# modulo_motores.net
KiCad netlist of a schematic drawn in EAGLE
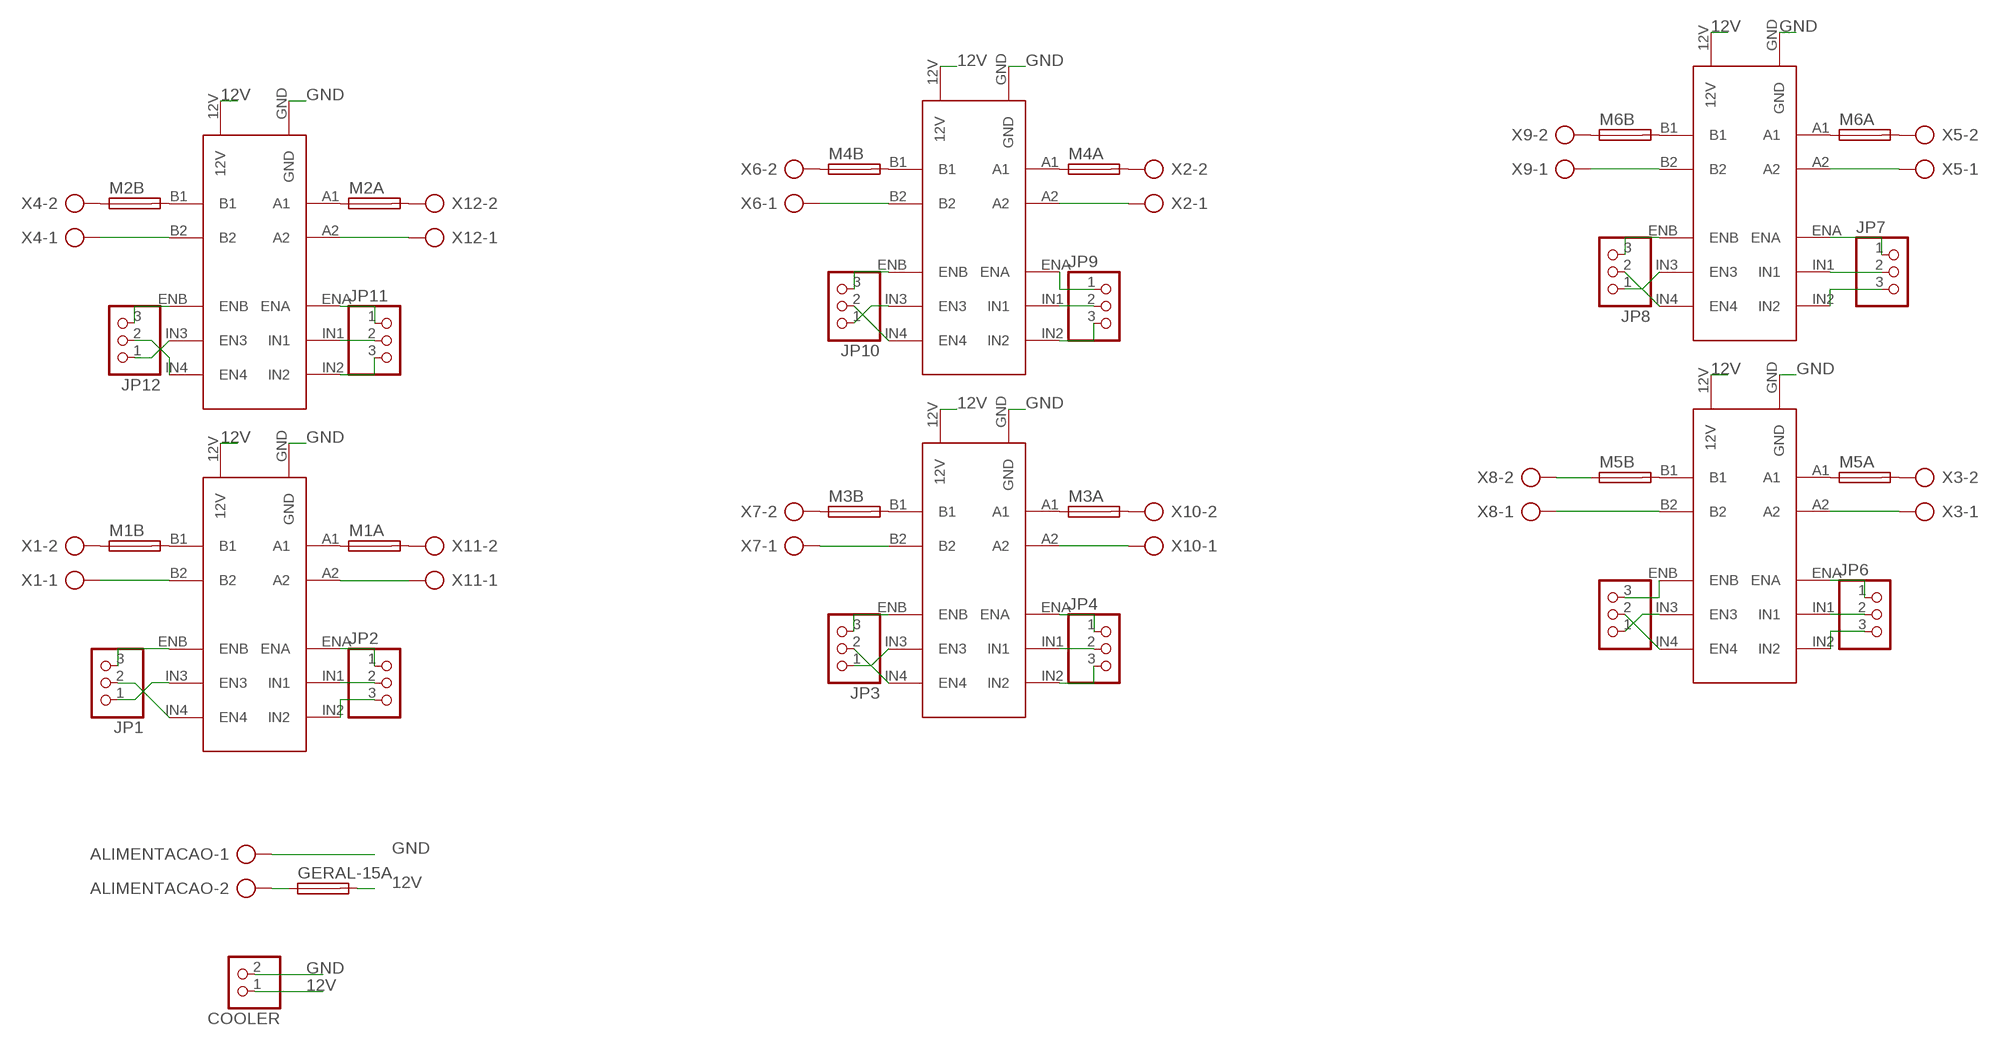
[diagram p0: schematic, sheet 1]

(export (version "E")
  (design (tool "Eeschema 10.0.6"))
  (components
    (comp (ref "ALIMENTACAO")
      (value "AK500/2")
      (footprint "eagle-import:AK500_2")
      (libsource (lib "eagle-import") (part "AK500/2"))
    )
    (comp (ref "COOLER")
      (value "PINHD-1X2")
      (footprint "eagle-import:1X02")
      (libsource (lib "eagle-import") (part "PINHD-1X2"))
    )
    (comp (ref "GERAL-15A")
      (value "SH22,5A")
      (footprint "eagle-import:SH22,5A")
      (fields (field (name "MPN") "0031.7701.11"))
      (libsource (lib "eagle-import") (part "SH22,5A"))
    )
    (comp (ref "JP1")
      (value "PINHD-1X3")
      (footprint "eagle-import:1X03")
      (libsource (lib "eagle-import") (part "PINHD-1X3"))
    )
    (comp (ref "JP2")
      (value "PINHD-1X3")
      (footprint "eagle-import:1X03")
      (libsource (lib "eagle-import") (part "PINHD-1X3"))
    )
    (comp (ref "JP3")
      (value "PINHD-1X3")
      (footprint "eagle-import:1X03")
      (libsource (lib "eagle-import") (part "PINHD-1X3"))
    )
    (comp (ref "JP4")
      (value "PINHD-1X3")
      (footprint "eagle-import:1X03")
      (libsource (lib "eagle-import") (part "PINHD-1X3"))
    )
    (comp (ref "JP5")
      (value "PINHD-1X3")
      (footprint "eagle-import:1X03")
      (libsource (lib "eagle-import") (part "PINHD-1X3"))
    )
    (comp (ref "JP6")
      (value "PINHD-1X3")
      (footprint "eagle-import:1X03")
      (libsource (lib "eagle-import") (part "PINHD-1X3"))
    )
    (comp (ref "JP7")
      (value "PINHD-1X3")
      (footprint "eagle-import:1X03")
      (libsource (lib "eagle-import") (part "PINHD-1X3"))
    )
    (comp (ref "JP8")
      (value "PINHD-1X3")
      (footprint "eagle-import:1X03")
      (libsource (lib "eagle-import") (part "PINHD-1X3"))
    )
    (comp (ref "JP9")
      (value "PINHD-1X3")
      (footprint "eagle-import:1X03")
      (libsource (lib "eagle-import") (part "PINHD-1X3"))
    )
    (comp (ref "JP10")
      (value "PINHD-1X3")
      (footprint "eagle-import:1X03")
      (libsource (lib "eagle-import") (part "PINHD-1X3"))
    )
    (comp (ref "JP11")
      (value "PINHD-1X3")
      (footprint "eagle-import:1X03")
      (libsource (lib "eagle-import") (part "PINHD-1X3"))
    )
    (comp (ref "JP12")
      (value "PINHD-1X3")
      (footprint "eagle-import:1X03")
      (libsource (lib "eagle-import") (part "PINHD-1X3"))
    )
    (comp (ref "M1")
      (value "L298N")
      (footprint "eagle-import:L298N")
      (libsource (lib "eagle-import") (part "L298N"))
    )
    (comp (ref "M1A")
      (value "SH22,5A")
      (footprint "eagle-import:SH22,5A")
      (fields (field (name "MPN") "0031.7701.11"))
      (libsource (lib "eagle-import") (part "SH22,5A"))
    )
    (comp (ref "M1B")
      (value "SH22,5A")
      (footprint "eagle-import:SH22,5A")
      (fields (field (name "MPN") "0031.7701.11"))
      (libsource (lib "eagle-import") (part "SH22,5A"))
    )
    (comp (ref "M2")
      (value "L298N")
      (footprint "eagle-import:L298N")
      (libsource (lib "eagle-import") (part "L298N"))
    )
    (comp (ref "M2A")
      (value "SH22,5A")
      (footprint "eagle-import:SH22,5A")
      (fields (field (name "MPN") "0031.7701.11"))
      (libsource (lib "eagle-import") (part "SH22,5A"))
    )
    (comp (ref "M2B")
      (value "SH22,5A")
      (footprint "eagle-import:SH22,5A")
      (fields (field (name "MPN") "0031.7701.11"))
      (libsource (lib "eagle-import") (part "SH22,5A"))
    )
    (comp (ref "M3")
      (value "L298N")
      (footprint "eagle-import:L298N")
      (libsource (lib "eagle-import") (part "L298N"))
    )
    (comp (ref "M3A")
      (value "SH22,5A")
      (footprint "eagle-import:SH22,5A")
      (fields (field (name "MPN") "0031.7701.11"))
      (libsource (lib "eagle-import") (part "SH22,5A"))
    )
    (comp (ref "M3B")
      (value "SH22,5A")
      (footprint "eagle-import:SH22,5A")
      (fields (field (name "MPN") "0031.7701.11"))
      (libsource (lib "eagle-import") (part "SH22,5A"))
    )
    (comp (ref "M4A")
      (value "SH22,5A")
      (footprint "eagle-import:SH22,5A")
      (fields (field (name "MPN") "0031.7701.11"))
      (libsource (lib "eagle-import") (part "SH22,5A"))
    )
    (comp (ref "M4B")
      (value "SH22,5A")
      (footprint "eagle-import:SH22,5A")
      (fields (field (name "MPN") "0031.7701.11"))
      (libsource (lib "eagle-import") (part "SH22,5A"))
    )
    (comp (ref "M5")
      (value "L298N")
      (footprint "eagle-import:L298N")
      (libsource (lib "eagle-import") (part "L298N"))
    )
    (comp (ref "M5A")
      (value "SH22,5A")
      (footprint "eagle-import:SH22,5A")
      (fields (field (name "MPN") "0031.7701.11"))
      (libsource (lib "eagle-import") (part "SH22,5A"))
    )
    (comp (ref "M5B")
      (value "SH22,5A")
      (footprint "eagle-import:SH22,5A")
      (fields (field (name "MPN") "0031.7701.11"))
      (libsource (lib "eagle-import") (part "SH22,5A"))
    )
    (comp (ref "M6")
      (value "L298N")
      (footprint "eagle-import:L298N")
      (libsource (lib "eagle-import") (part "L298N"))
    )
    (comp (ref "M6A")
      (value "SH22,5A")
      (footprint "eagle-import:SH22,5A")
      (fields (field (name "MPN") "0031.7701.11"))
      (libsource (lib "eagle-import") (part "SH22,5A"))
    )
    (comp (ref "M6B")
      (value "SH22,5A")
      (footprint "eagle-import:SH22,5A")
      (fields (field (name "MPN") "0031.7701.11"))
      (libsource (lib "eagle-import") (part "SH22,5A"))
    )
    (comp (ref "U$2")
      (value "L298N")
      (footprint "eagle-import:L298N")
      (libsource (lib "eagle-import") (part "L298N"))
    )
    (comp (ref "X1")
      (value "AK500/2")
      (footprint "eagle-import:AK500_2")
      (libsource (lib "eagle-import") (part "AK500/2"))
    )
    (comp (ref "X2")
      (value "AK500/2")
      (footprint "eagle-import:AK500_2")
      (libsource (lib "eagle-import") (part "AK500/2"))
    )
    (comp (ref "X3")
      (value "AK500/2")
      (footprint "eagle-import:AK500_2")
      (libsource (lib "eagle-import") (part "AK500/2"))
    )
    (comp (ref "X4")
      (value "AK500/2")
      (footprint "eagle-import:AK500_2")
      (libsource (lib "eagle-import") (part "AK500/2"))
    )
    (comp (ref "X5")
      (value "AK500/2")
      (footprint "eagle-import:AK500_2")
      (libsource (lib "eagle-import") (part "AK500/2"))
    )
    (comp (ref "X6")
      (value "AK500/2")
      (footprint "eagle-import:AK500_2")
      (libsource (lib "eagle-import") (part "AK500/2"))
    )
    (comp (ref "X7")
      (value "AK500/2")
      (footprint "eagle-import:AK500_2")
      (libsource (lib "eagle-import") (part "AK500/2"))
    )
    (comp (ref "X8")
      (value "AK500/2")
      (footprint "eagle-import:AK500_2")
      (libsource (lib "eagle-import") (part "AK500/2"))
    )
    (comp (ref "X9")
      (value "AK500/2")
      (footprint "eagle-import:AK500_2")
      (libsource (lib "eagle-import") (part "AK500/2"))
    )
    (comp (ref "X10")
      (value "AK500/2")
      (footprint "eagle-import:AK500_2")
      (libsource (lib "eagle-import") (part "AK500/2"))
    )
    (comp (ref "X11")
      (value "AK500/2")
      (footprint "eagle-import:AK500_2")
      (libsource (lib "eagle-import") (part "AK500/2"))
    )
    (comp (ref "X12")
      (value "AK500/2")
      (footprint "eagle-import:AK500_2")
      (libsource (lib "eagle-import") (part "AK500/2"))
    )
  )
  (nets
    (net (code "1") (name "/12V") (class "Default")
      (node (ref "COOLER") (pin "1") (pinfunction "1_1") (pintype "passive"))
      (node (ref "GERAL-15A") (pin "2") (pinfunction "2_2") (pintype "passive"))
      (node (ref "M1") (pin "12V") (pinfunction "12V_12V") (pintype "bidirectional"))
      (node (ref "M2") (pin "12V") (pinfunction "12V_12V") (pintype "bidirectional"))
      (node (ref "M3") (pin "12V") (pinfunction "12V_12V") (pintype "bidirectional"))
      (node (ref "M5") (pin "12V") (pinfunction "12V_12V") (pintype "bidirectional"))
      (node (ref "M6") (pin "12V") (pinfunction "12V_12V") (pintype "bidirectional"))
      (node (ref "U$2") (pin "12V") (pinfunction "12V_12V") (pintype "bidirectional"))
    )
    (net (code "2") (name "/GND") (class "Default")
      (node (ref "ALIMENTACAO") (pin "1") (pinfunction "KL_1") (pintype "passive"))
      (node (ref "COOLER") (pin "2") (pinfunction "2_2") (pintype "passive"))
      (node (ref "M1") (pin "GND") (pinfunction "GND_GND") (pintype "bidirectional"))
      (node (ref "M2") (pin "GND") (pinfunction "GND_GND") (pintype "bidirectional"))
      (node (ref "M3") (pin "GND") (pinfunction "GND_GND") (pintype "bidirectional"))
      (node (ref "M5") (pin "GND") (pinfunction "GND_GND") (pintype "bidirectional"))
      (node (ref "M6") (pin "GND") (pinfunction "GND_GND") (pintype "bidirectional"))
      (node (ref "U$2") (pin "GND") (pinfunction "GND_GND") (pintype "bidirectional"))
    )
    (net (code "3") (name "Net-(ALIMENTACAOB-KL)") (class "Default")
      (node (ref "ALIMENTACAO") (pin "2") (pinfunction "KL_2") (pintype "passive"))
      (node (ref "GERAL-15A") (pin "1") (pinfunction "1_1") (pintype "passive"))
    )
    (net (code "4") (name "Net-(JP1-Pad3)") (class "Default")
      (node (ref "JP1") (pin "3") (pinfunction "3_3") (pintype "passive"))
      (node (ref "M1") (pin "ENB") (pinfunction "ENB_ENB") (pintype "bidirectional"))
    )
    (net (code "5") (name "Net-(JP2-Pad1)") (class "Default")
      (node (ref "JP2") (pin "1") (pinfunction "1_1") (pintype "passive"))
      (node (ref "M1") (pin "ENA") (pinfunction "ENA_ENA") (pintype "bidirectional"))
    )
    (net (code "6") (name "Net-(JP2-Pad2)") (class "Default")
      (node (ref "JP2") (pin "2") (pinfunction "2_2") (pintype "passive"))
      (node (ref "M1") (pin "IN1") (pinfunction "IN1_IN1") (pintype "bidirectional"))
    )
    (net (code "7") (name "Net-(JP2-Pad3)") (class "Default")
      (node (ref "JP2") (pin "3") (pinfunction "3_3") (pintype "passive"))
      (node (ref "M1") (pin "IN2") (pinfunction "IN2_IN2") (pintype "bidirectional"))
    )
    (net (code "8") (name "Net-(JP3-Pad3)") (class "Default")
      (node (ref "JP3") (pin "3") (pinfunction "3_3") (pintype "passive"))
      (node (ref "M3") (pin "ENB") (pinfunction "ENB_ENB") (pintype "bidirectional"))
    )
    (net (code "9") (name "Net-(JP4-Pad1)") (class "Default")
      (node (ref "JP4") (pin "1") (pinfunction "1_1") (pintype "passive"))
      (node (ref "M3") (pin "ENA") (pinfunction "ENA_ENA") (pintype "bidirectional"))
    )
    (net (code "10") (name "Net-(JP4-Pad2)") (class "Default")
      (node (ref "JP4") (pin "2") (pinfunction "2_2") (pintype "passive"))
      (node (ref "M3") (pin "IN1") (pinfunction "IN1_IN1") (pintype "bidirectional"))
    )
    (net (code "11") (name "Net-(JP4-Pad3)") (class "Default")
      (node (ref "JP4") (pin "3") (pinfunction "3_3") (pintype "passive"))
      (node (ref "M3") (pin "IN2") (pinfunction "IN2_IN2") (pintype "bidirectional"))
    )
    (net (code "12") (name "Net-(JP5-Pad3)") (class "Default")
      (node (ref "JP5") (pin "3") (pinfunction "3_3") (pintype "passive"))
      (node (ref "M5") (pin "ENB") (pinfunction "ENB_ENB") (pintype "bidirectional"))
    )
    (net (code "13") (name "Net-(JP6-Pad1)") (class "Default")
      (node (ref "JP6") (pin "1") (pinfunction "1_1") (pintype "passive"))
      (node (ref "M5") (pin "ENA") (pinfunction "ENA_ENA") (pintype "bidirectional"))
    )
    (net (code "14") (name "Net-(JP6-Pad2)") (class "Default")
      (node (ref "JP6") (pin "2") (pinfunction "2_2") (pintype "passive"))
      (node (ref "M5") (pin "IN1") (pinfunction "IN1_IN1") (pintype "bidirectional"))
    )
    (net (code "15") (name "Net-(JP6-Pad3)") (class "Default")
      (node (ref "JP6") (pin "3") (pinfunction "3_3") (pintype "passive"))
      (node (ref "M5") (pin "IN2") (pinfunction "IN2_IN2") (pintype "bidirectional"))
    )
    (net (code "16") (name "Net-(JP7-Pad1)") (class "Default")
      (node (ref "JP7") (pin "1") (pinfunction "1_1") (pintype "passive"))
      (node (ref "M6") (pin "ENA") (pinfunction "ENA_ENA") (pintype "bidirectional"))
    )
    (net (code "17") (name "Net-(JP7-Pad2)") (class "Default")
      (node (ref "JP7") (pin "2") (pinfunction "2_2") (pintype "passive"))
      (node (ref "M6") (pin "IN1") (pinfunction "IN1_IN1") (pintype "bidirectional"))
    )
    (net (code "18") (name "Net-(JP7-Pad3)") (class "Default")
      (node (ref "JP7") (pin "3") (pinfunction "3_3") (pintype "passive"))
      (node (ref "M6") (pin "IN2") (pinfunction "IN2_IN2") (pintype "bidirectional"))
    )
    (net (code "19") (name "Net-(JP8-Pad3)") (class "Default")
      (node (ref "JP8") (pin "3") (pinfunction "3_3") (pintype "passive"))
      (node (ref "M6") (pin "ENB") (pinfunction "ENB_ENB") (pintype "bidirectional"))
    )
    (net (code "20") (name "Net-(JP9-Pad1)") (class "Default")
      (node (ref "JP9") (pin "1") (pinfunction "1_1") (pintype "passive"))
      (node (ref "U$2") (pin "ENA") (pinfunction "ENA_ENA") (pintype "bidirectional"))
    )
    (net (code "21") (name "Net-(JP9-Pad2)") (class "Default")
      (node (ref "JP9") (pin "2") (pinfunction "2_2") (pintype "passive"))
      (node (ref "U$2") (pin "IN1") (pinfunction "IN1_IN1") (pintype "bidirectional"))
    )
    (net (code "22") (name "Net-(JP9-Pad3)") (class "Default")
      (node (ref "JP9") (pin "3") (pinfunction "3_3") (pintype "passive"))
      (node (ref "U$2") (pin "IN2") (pinfunction "IN2_IN2") (pintype "bidirectional"))
    )
    (net (code "23") (name "Net-(JP10-Pad3)") (class "Default")
      (node (ref "JP10") (pin "3") (pinfunction "3_3") (pintype "passive"))
      (node (ref "U$2") (pin "ENB") (pinfunction "ENB_ENB") (pintype "bidirectional"))
    )
    (net (code "24") (name "Net-(JP11-Pad1)") (class "Default")
      (node (ref "JP11") (pin "1") (pinfunction "1_1") (pintype "passive"))
      (node (ref "M2") (pin "ENA") (pinfunction "ENA_ENA") (pintype "bidirectional"))
    )
    (net (code "25") (name "Net-(JP11-Pad2)") (class "Default")
      (node (ref "JP11") (pin "2") (pinfunction "2_2") (pintype "passive"))
      (node (ref "M2") (pin "IN1") (pinfunction "IN1_IN1") (pintype "bidirectional"))
    )
    (net (code "26") (name "Net-(JP11-Pad3)") (class "Default")
      (node (ref "JP11") (pin "3") (pinfunction "3_3") (pintype "passive"))
      (node (ref "M2") (pin "IN2") (pinfunction "IN2_IN2") (pintype "bidirectional"))
    )
    (net (code "27") (name "Net-(JP12-Pad3)") (class "Default")
      (node (ref "JP12") (pin "3") (pinfunction "3_3") (pintype "passive"))
      (node (ref "M2") (pin "ENB") (pinfunction "ENB_ENB") (pintype "bidirectional"))
    )
    (net (code "28") (name "Net-(M1-EN3)") (class "Default")
      (node (ref "JP1") (pin "1") (pinfunction "1_1") (pintype "passive"))
      (node (ref "M1") (pin "IN3") (pinfunction "EN3_IN3") (pintype "bidirectional"))
    )
    (net (code "29") (name "Net-(M1-EN4)") (class "Default")
      (node (ref "JP1") (pin "2") (pinfunction "2_2") (pintype "passive"))
      (node (ref "M1") (pin "IN4") (pinfunction "EN4_IN4") (pintype "bidirectional"))
    )
    (net (code "30") (name "Net-(M1-PadA1)") (class "Default")
      (node (ref "M1") (pin "A1") (pinfunction "A1_A1") (pintype "bidirectional"))
      (node (ref "M1A") (pin "1") (pinfunction "1_1") (pintype "passive"))
    )
    (net (code "31") (name "Net-(M1-PadB1)") (class "Default")
      (node (ref "M1") (pin "B1") (pinfunction "B1_B1") (pintype "bidirectional"))
      (node (ref "M1B") (pin "2") (pinfunction "2_2") (pintype "passive"))
    )
    (net (code "32") (name "Net-(M2-EN3)") (class "Default")
      (node (ref "JP12") (pin "1") (pinfunction "1_1") (pintype "passive"))
      (node (ref "M2") (pin "IN3") (pinfunction "EN3_IN3") (pintype "bidirectional"))
    )
    (net (code "33") (name "Net-(M2-EN4)") (class "Default")
      (node (ref "JP12") (pin "2") (pinfunction "2_2") (pintype "passive"))
      (node (ref "M2") (pin "IN4") (pinfunction "EN4_IN4") (pintype "bidirectional"))
    )
    (net (code "34") (name "Net-(M2-PadA1)") (class "Default")
      (node (ref "M2") (pin "A1") (pinfunction "A1_A1") (pintype "bidirectional"))
      (node (ref "M2A") (pin "1") (pinfunction "1_1") (pintype "passive"))
    )
    (net (code "35") (name "Net-(M2-PadB1)") (class "Default")
      (node (ref "M2") (pin "B1") (pinfunction "B1_B1") (pintype "bidirectional"))
      (node (ref "M2B") (pin "2") (pinfunction "2_2") (pintype "passive"))
    )
    (net (code "36") (name "Net-(M3-EN3)") (class "Default")
      (node (ref "JP3") (pin "1") (pinfunction "1_1") (pintype "passive"))
      (node (ref "M3") (pin "IN3") (pinfunction "EN3_IN3") (pintype "bidirectional"))
    )
    (net (code "37") (name "Net-(M3-EN4)") (class "Default")
      (node (ref "JP3") (pin "2") (pinfunction "2_2") (pintype "passive"))
      (node (ref "M3") (pin "IN4") (pinfunction "EN4_IN4") (pintype "bidirectional"))
    )
    (net (code "38") (name "Net-(M3-PadA1)") (class "Default")
      (node (ref "M3") (pin "A1") (pinfunction "A1_A1") (pintype "bidirectional"))
      (node (ref "M3A") (pin "1") (pinfunction "1_1") (pintype "passive"))
    )
    (net (code "39") (name "Net-(M3-PadB1)") (class "Default")
      (node (ref "M3") (pin "B1") (pinfunction "B1_B1") (pintype "bidirectional"))
      (node (ref "M3B") (pin "2") (pinfunction "2_2") (pintype "passive"))
    )
    (net (code "40") (name "Net-(M4A-Pad1)") (class "Default")
      (node (ref "M4A") (pin "1") (pinfunction "1_1") (pintype "passive"))
      (node (ref "U$2") (pin "A1") (pinfunction "A1_A1") (pintype "bidirectional"))
    )
    (net (code "41") (name "Net-(M4B-Pad2)") (class "Default")
      (node (ref "M4B") (pin "2") (pinfunction "2_2") (pintype "passive"))
      (node (ref "U$2") (pin "B1") (pinfunction "B1_B1") (pintype "bidirectional"))
    )
    (net (code "42") (name "Net-(M5-EN3)") (class "Default")
      (node (ref "JP5") (pin "1") (pinfunction "1_1") (pintype "passive"))
      (node (ref "M5") (pin "IN3") (pinfunction "EN3_IN3") (pintype "bidirectional"))
    )
    (net (code "43") (name "Net-(M5-EN4)") (class "Default")
      (node (ref "JP5") (pin "2") (pinfunction "2_2") (pintype "passive"))
      (node (ref "M5") (pin "IN4") (pinfunction "EN4_IN4") (pintype "bidirectional"))
    )
    (net (code "44") (name "Net-(M5-PadA1)") (class "Default")
      (node (ref "M5") (pin "A1") (pinfunction "A1_A1") (pintype "bidirectional"))
      (node (ref "M5A") (pin "1") (pinfunction "1_1") (pintype "passive"))
    )
    (net (code "45") (name "Net-(M5-PadB1)") (class "Default")
      (node (ref "M5") (pin "B1") (pinfunction "B1_B1") (pintype "bidirectional"))
      (node (ref "M5B") (pin "2") (pinfunction "2_2") (pintype "passive"))
    )
    (net (code "46") (name "Net-(M6-EN3)") (class "Default")
      (node (ref "JP8") (pin "1") (pinfunction "1_1") (pintype "passive"))
      (node (ref "M6") (pin "IN3") (pinfunction "EN3_IN3") (pintype "bidirectional"))
    )
    (net (code "47") (name "Net-(M6-EN4)") (class "Default")
      (node (ref "JP8") (pin "2") (pinfunction "2_2") (pintype "passive"))
      (node (ref "M6") (pin "IN4") (pinfunction "EN4_IN4") (pintype "bidirectional"))
    )
    (net (code "48") (name "Net-(M6-PadA1)") (class "Default")
      (node (ref "M6") (pin "A1") (pinfunction "A1_A1") (pintype "bidirectional"))
      (node (ref "M6A") (pin "1") (pinfunction "1_1") (pintype "passive"))
    )
    (net (code "49") (name "Net-(M6-PadB1)") (class "Default")
      (node (ref "M6") (pin "B1") (pinfunction "B1_B1") (pintype "bidirectional"))
      (node (ref "M6B") (pin "2") (pinfunction "2_2") (pintype "passive"))
    )
    (net (code "50") (name "Net-(U$2-EN3)") (class "Default")
      (node (ref "JP10") (pin "1") (pinfunction "1_1") (pintype "passive"))
      (node (ref "U$2") (pin "IN3") (pinfunction "EN3_IN3") (pintype "bidirectional"))
    )
    (net (code "51") (name "Net-(U$2-EN4)") (class "Default")
      (node (ref "JP10") (pin "2") (pinfunction "2_2") (pintype "passive"))
      (node (ref "U$2") (pin "IN4") (pinfunction "EN4_IN4") (pintype "bidirectional"))
    )
    (net (code "52") (name "Net-(X1A-KL)") (class "Default")
      (node (ref "M1") (pin "B2") (pinfunction "B2_B2") (pintype "bidirectional"))
      (node (ref "X1") (pin "1") (pinfunction "KL_1") (pintype "passive"))
    )
    (net (code "53") (name "Net-(X1B-KL)") (class "Default")
      (node (ref "M1B") (pin "1") (pinfunction "1_1") (pintype "passive"))
      (node (ref "X1") (pin "2") (pinfunction "KL_2") (pintype "passive"))
    )
    (net (code "54") (name "Net-(X2A-KL)") (class "Default")
      (node (ref "U$2") (pin "A2") (pinfunction "A2_A2") (pintype "bidirectional"))
      (node (ref "X2") (pin "1") (pinfunction "KL_1") (pintype "passive"))
    )
    (net (code "55") (name "Net-(X2B-KL)") (class "Default")
      (node (ref "M4A") (pin "2") (pinfunction "2_2") (pintype "passive"))
      (node (ref "X2") (pin "2") (pinfunction "KL_2") (pintype "passive"))
    )
    (net (code "56") (name "Net-(X3A-KL)") (class "Default")
      (node (ref "M5") (pin "A2") (pinfunction "A2_A2") (pintype "bidirectional"))
      (node (ref "X3") (pin "1") (pinfunction "KL_1") (pintype "passive"))
    )
    (net (code "57") (name "Net-(X3B-KL)") (class "Default")
      (node (ref "M5A") (pin "2") (pinfunction "2_2") (pintype "passive"))
      (node (ref "X3") (pin "2") (pinfunction "KL_2") (pintype "passive"))
    )
    (net (code "58") (name "Net-(X4A-KL)") (class "Default")
      (node (ref "M2") (pin "B2") (pinfunction "B2_B2") (pintype "bidirectional"))
      (node (ref "X4") (pin "1") (pinfunction "KL_1") (pintype "passive"))
    )
    (net (code "59") (name "Net-(X4B-KL)") (class "Default")
      (node (ref "M2B") (pin "1") (pinfunction "1_1") (pintype "passive"))
      (node (ref "X4") (pin "2") (pinfunction "KL_2") (pintype "passive"))
    )
    (net (code "60") (name "Net-(X5A-KL)") (class "Default")
      (node (ref "M6") (pin "A2") (pinfunction "A2_A2") (pintype "bidirectional"))
      (node (ref "X5") (pin "1") (pinfunction "KL_1") (pintype "passive"))
    )
    (net (code "61") (name "Net-(X5B-KL)") (class "Default")
      (node (ref "M6A") (pin "2") (pinfunction "2_2") (pintype "passive"))
      (node (ref "X5") (pin "2") (pinfunction "KL_2") (pintype "passive"))
    )
    (net (code "62") (name "Net-(X6A-KL)") (class "Default")
      (node (ref "U$2") (pin "B2") (pinfunction "B2_B2") (pintype "bidirectional"))
      (node (ref "X6") (pin "1") (pinfunction "KL_1") (pintype "passive"))
    )
    (net (code "63") (name "Net-(X6B-KL)") (class "Default")
      (node (ref "M4B") (pin "1") (pinfunction "1_1") (pintype "passive"))
      (node (ref "X6") (pin "2") (pinfunction "KL_2") (pintype "passive"))
    )
    (net (code "64") (name "Net-(X7A-KL)") (class "Default")
      (node (ref "M3") (pin "B2") (pinfunction "B2_B2") (pintype "bidirectional"))
      (node (ref "X7") (pin "1") (pinfunction "KL_1") (pintype "passive"))
    )
    (net (code "65") (name "Net-(X7B-KL)") (class "Default")
      (node (ref "M3B") (pin "1") (pinfunction "1_1") (pintype "passive"))
      (node (ref "X7") (pin "2") (pinfunction "KL_2") (pintype "passive"))
    )
    (net (code "66") (name "Net-(X8A-KL)") (class "Default")
      (node (ref "M5") (pin "B2") (pinfunction "B2_B2") (pintype "bidirectional"))
      (node (ref "X8") (pin "1") (pinfunction "KL_1") (pintype "passive"))
    )
    (net (code "67") (name "Net-(X8B-KL)") (class "Default")
      (node (ref "M5B") (pin "1") (pinfunction "1_1") (pintype "passive"))
      (node (ref "X8") (pin "2") (pinfunction "KL_2") (pintype "passive"))
    )
    (net (code "68") (name "Net-(X9A-KL)") (class "Default")
      (node (ref "M6") (pin "B2") (pinfunction "B2_B2") (pintype "bidirectional"))
      (node (ref "X9") (pin "1") (pinfunction "KL_1") (pintype "passive"))
    )
    (net (code "69") (name "Net-(X9B-KL)") (class "Default")
      (node (ref "M6B") (pin "1") (pinfunction "1_1") (pintype "passive"))
      (node (ref "X9") (pin "2") (pinfunction "KL_2") (pintype "passive"))
    )
    (net (code "70") (name "Net-(X10A-KL)") (class "Default")
      (node (ref "M3") (pin "A2") (pinfunction "A2_A2") (pintype "bidirectional"))
      (node (ref "X10") (pin "1") (pinfunction "KL_1") (pintype "passive"))
    )
    (net (code "71") (name "Net-(X10B-KL)") (class "Default")
      (node (ref "M3A") (pin "2") (pinfunction "2_2") (pintype "passive"))
      (node (ref "X10") (pin "2") (pinfunction "KL_2") (pintype "passive"))
    )
    (net (code "72") (name "Net-(X11A-KL)") (class "Default")
      (node (ref "M1") (pin "A2") (pinfunction "A2_A2") (pintype "bidirectional"))
      (node (ref "X11") (pin "1") (pinfunction "KL_1") (pintype "passive"))
    )
    (net (code "73") (name "Net-(X11B-KL)") (class "Default")
      (node (ref "M1A") (pin "2") (pinfunction "2_2") (pintype "passive"))
      (node (ref "X11") (pin "2") (pinfunction "KL_2") (pintype "passive"))
    )
    (net (code "74") (name "Net-(X12A-KL)") (class "Default")
      (node (ref "M2") (pin "A2") (pinfunction "A2_A2") (pintype "bidirectional"))
      (node (ref "X12") (pin "1") (pinfunction "KL_1") (pintype "passive"))
    )
    (net (code "75") (name "Net-(X12B-KL)") (class "Default")
      (node (ref "M2A") (pin "2") (pinfunction "2_2") (pintype "passive"))
      (node (ref "X12") (pin "2") (pinfunction "KL_2") (pintype "passive"))
    )
  )
)
